# FPGA_BANK_A.net
KiCad netlist of a schematic drawn in Altium Designer
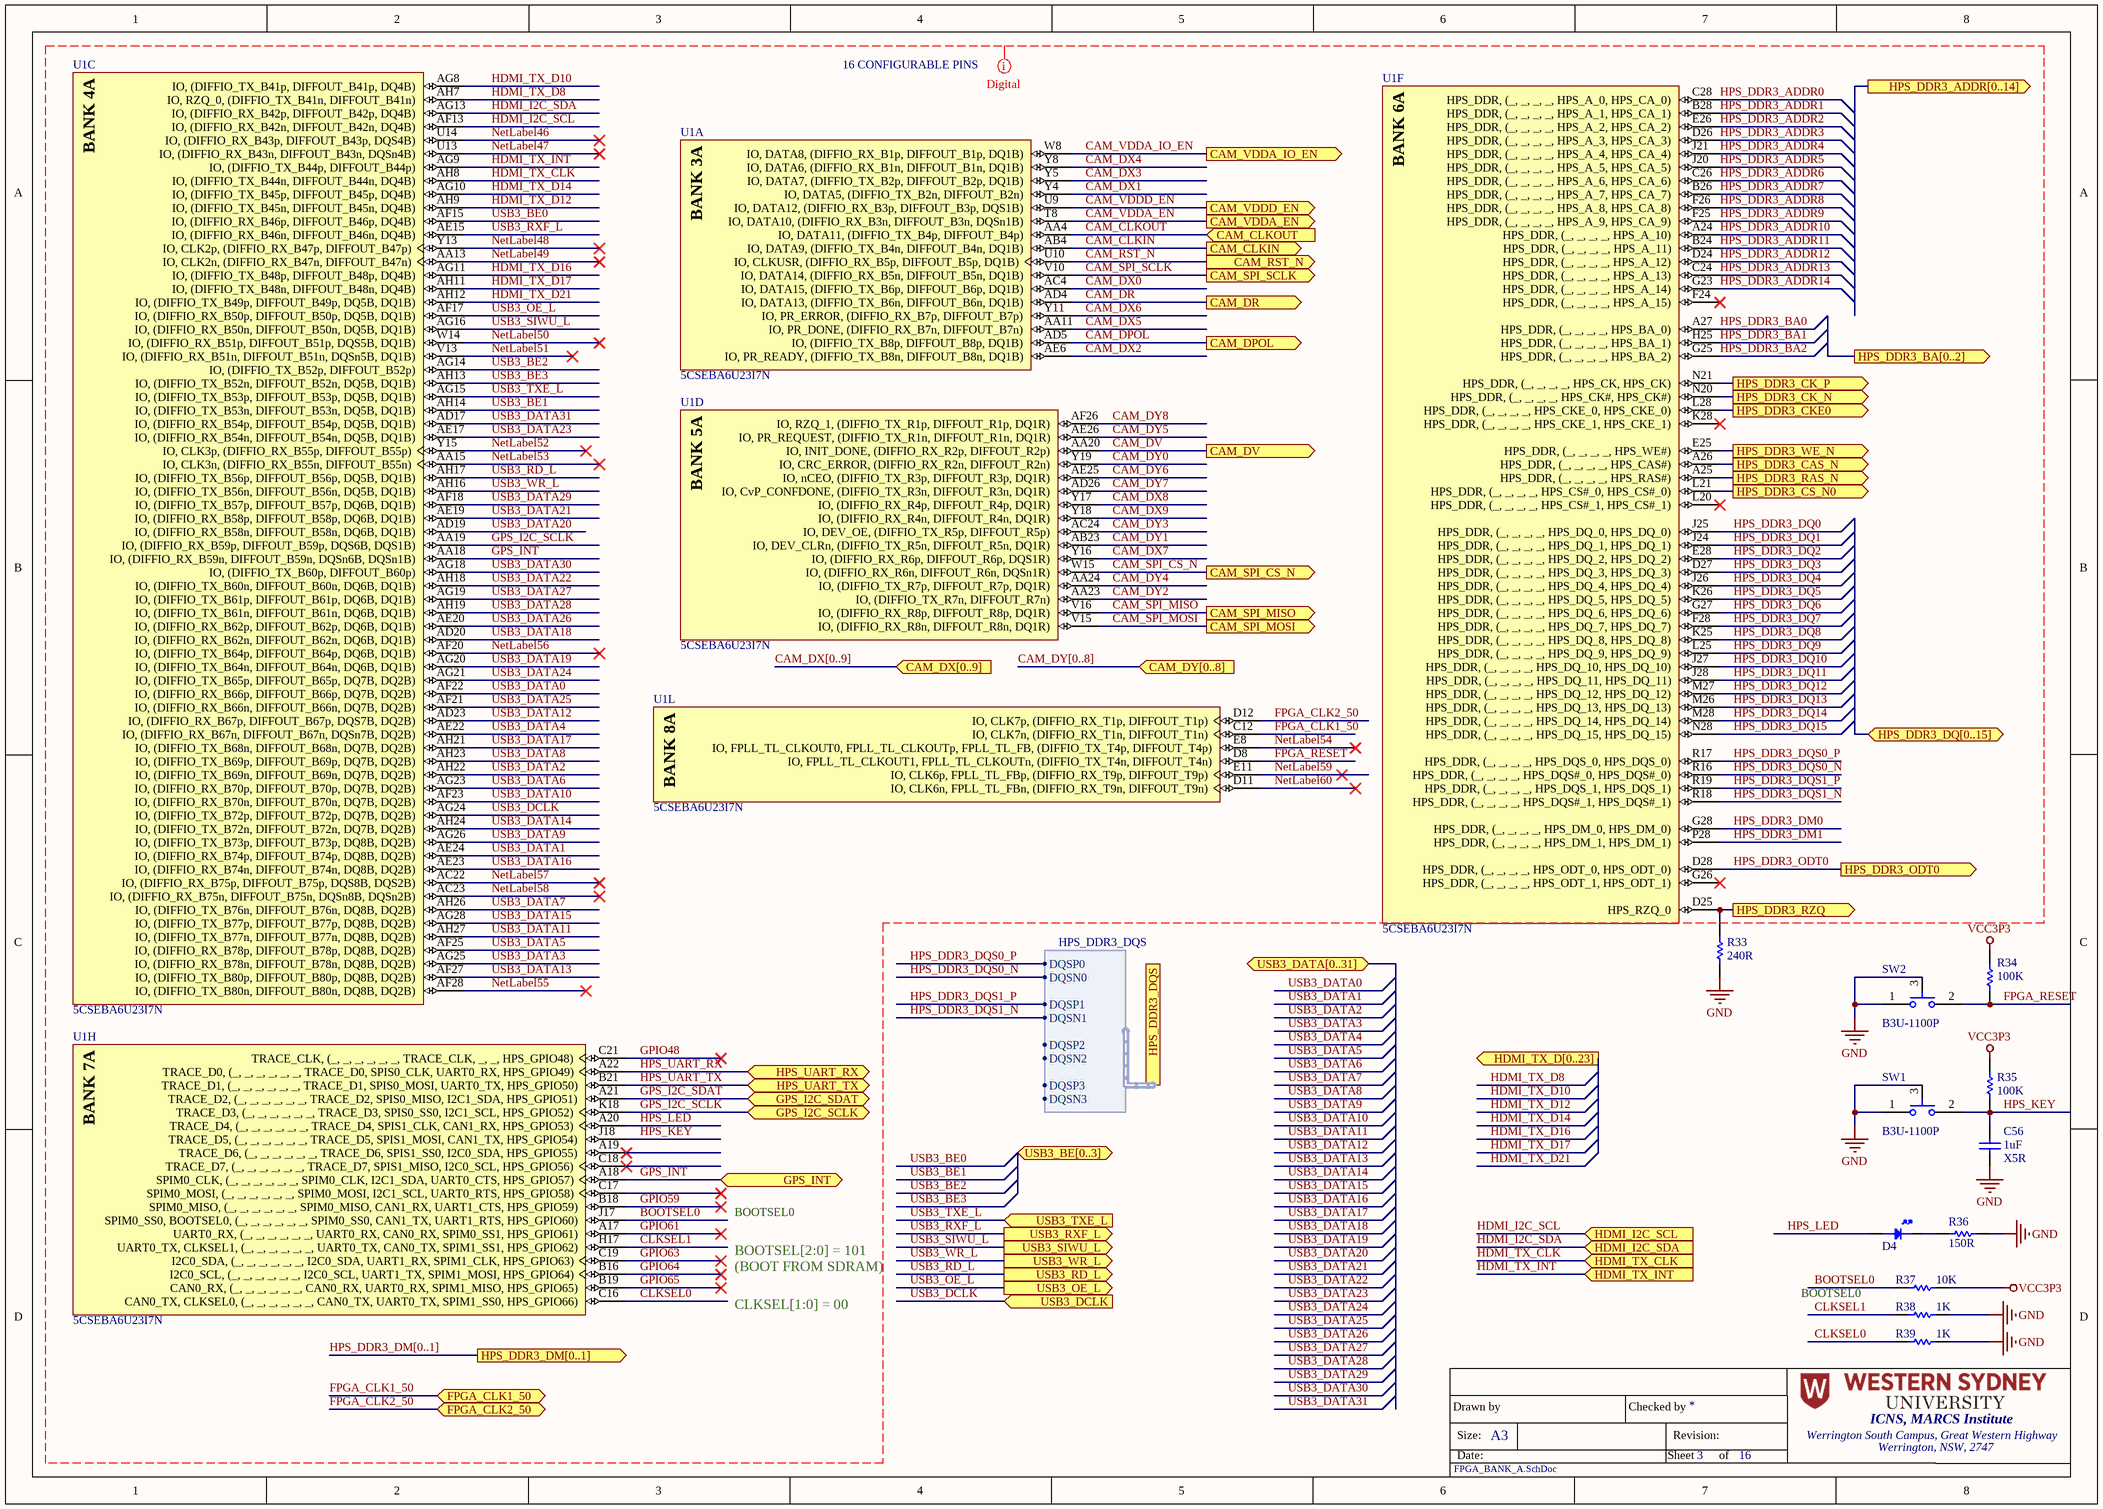
[diagram p0: FPGA_BANK_A.SchDoc]

(export (version "E")
  (design (tool "Eeschema 10.0.6"))
  (components
    (comp (ref "C56")
      (value "1uF")
      (footprint "CAP 0201 (0603)")
      (description "Cap Ceramic 1uF 10V X5R 10% Pad SMD 0201 85C T/R")
      (fields
        (field (name "MANUFACTURER") "Samsung")
        (field (name "TOLERANCE") "10%")
        (field (name "DIELECTRIC") "X5R")
        (field (name "SOURCE") "ICNS_PropheseeLib.SchLib")
      )
      (libsource (lib "") (part "Symbol_1"))
    )
    (comp (ref "D4")
      (value "150060SS75000")
      (footprint "DIOC 0603 (1608)")
      (description "Led, Red, 630 Nm, 1.9 V, 20mA, 30 Ma, 60 Mcd Rohs Compliant: Yes")
      (fields (field (name "SOURCE") "ICNS_PropheseeLib.SchLib"))
      (libsource (lib "Western Sydney University - ICNS") (part "150060SS75000"))
    )
    (comp (ref "R33")
      (value "240R")
      (footprint "RES 0201 (0603)")
      (description "Res Thick Film 0201 240 Ohm 1% 0.05W(1/20W) ±200ppm/C Pad SMD Automotive T/R")
      (fields
        (field (name "MANUFACTURER") "Yageo")
        (field (name "TOLERANCE") "1%")
        (field (name "SOURCE") "ICNS_PropheseeLib.SchLib")
      )
      (libsource (lib "Western Sydney University - ICNS") (part "Symbol"))
    )
    (comp (ref "R34")
      (value "100K")
      (footprint "RES 0402 (1005)")
      (description "Res Thick Film 0402 100K Ohm 1% 0.2W(1/5W) ±100ppm/C Pad SMD Automotive T/R")
      (fields
        (field (name "TOLERANCE") "1%")
        (field (name "Comment") "CRCW0402100KFKEDHP")
        (field (name "SOURCE") "ICNS_PropheseeLib.SchLib")
      )
      (libsource (lib "Western Sydney University - ICNS") (part "Symbol"))
    )
    (comp (ref "R35")
      (value "100K")
      (footprint "RES 0402 (1005)")
      (description "Res Thick Film 0402 100K Ohm 1% 0.2W(1/5W) ±100ppm/C Pad SMD Automotive T/R")
      (fields
        (field (name "TOLERANCE") "1%")
        (field (name "Comment") "CRCW0402100KFKEDHP")
        (field (name "SOURCE") "ICNS_PropheseeLib.SchLib")
      )
      (libsource (lib "Western Sydney University - ICNS") (part "Symbol"))
    )
    (comp (ref "R36")
      (value "AC0603FR-10150RL")
      (footprint "RES 0603 (1608)")
      (description "Chip Resistor Automotive Grade Thick Film 0603 150Ohm 1% Paper T/R")
      (fields
        (field (name "MANUFACTURER") "Yageo")
        (field (name "RESISTANCE") "150R")
        (field (name "TOLERANCE") "1%")
        (field (name "SOURCE") "ICNS_PropheseeLib.SchLib")
      )
      (libsource (lib "Western Sydney University - ICNS") (part "AC0603FR-10150RL"))
    )
    (comp (ref "R37")
      (value "10K")
      (footprint "RES 0201 (0603)")
      (description "Res Thick Film 0201 10K Ohm 1% 0.05W(1/20W) ±200ppm/C Pad SMD Automotive T/R")
      (fields
        (field (name "TOLERANCE") "1%")
        (field (name "MANUFACTURER PART NUMBER") "AC0201FR-0710KL")
        (field (name "SOURCE") "ICNS_PropheseeLib.SchLib")
      )
      (libsource (lib "Western Sydney University - ICNS") (part "Symbol"))
    )
    (comp (ref "R38")
      (value "1K")
      (footprint "RES 0201 (0603)")
      (description "Res Thick Film 0201 1K Ohm 1% 0.05W(1/20W) ±200ppm/C Pad SMD Automotive T/R")
      (fields
        (field (name "MANUFACTURER") "Yageo")
        (field (name "TOLERANCE") "1%")
        (field (name "SOURCE") "ICNS_PropheseeLib.SchLib")
      )
      (libsource (lib "Western Sydney University - ICNS") (part "Symbol"))
    )
    (comp (ref "R39")
      (value "1K")
      (footprint "RES 0201 (0603)")
      (description "Res Thick Film 0201 1K Ohm 1% 0.05W(1/20W) ±200ppm/C Pad SMD Automotive T/R")
      (fields
        (field (name "MANUFACTURER") "Yageo")
        (field (name "TOLERANCE") "1%")
        (field (name "SOURCE") "ICNS_PropheseeLib.SchLib")
      )
      (libsource (lib "Western Sydney University - ICNS") (part "Symbol"))
    )
    (comp (ref "SW1")
      (value "B3U-1100P")
      (footprint "FP-B3U-1100P-MFG")
      (description "Switch Tactile N.O. SPST Round Button Gull Wing 0.05A 12VDC 1.5N SMD Embossed T/R")
      (fields (field (name "MANUFACTURER") "Omron") (field (name "SOURCE") "ICNS_PropheseeLib.SchLib"))
      (libsource (lib "Western Sydney University - ICNS") (part "B3U-1100P"))
    )
    (comp (ref "SW2")
      (value "B3U-1100P")
      (footprint "FP-B3U-1100P-MFG")
      (description "Switch Tactile N.O. SPST Round Button Gull Wing 0.05A 12VDC 1.5N SMD Embossed T/R")
      (fields (field (name "MANUFACTURER") "Omron") (field (name "SOURCE") "ICNS_PropheseeLib.SchLib"))
      (libsource (lib "Western Sydney University - ICNS") (part "B3U-1100P"))
    )
    (comp (ref "U1")
      (value "5CSEBA6U23I7N")
      (footprint "ALTR-UBGA672_A-185")
      (fields (field (name "MANUFACTURER") "Altera") (field (name "SOURCE") "ICNS_PropheseeLib.SchLib"))
      (libsource (lib "Western Sydney University - ICNS") (part "5CSEBA6U23I7N"))
    )
  )
  (nets
    (net (code "19") (name "/BOOTSEL0") (class "Default")
      (node (ref "R37") (pin "2") (pinfunction "2_2") (pintype "passive"))
      (node (ref "U1") (pin "J17") (pinfunction "SPIM0_SS0,_BOOTSEL0,_(_,__,__,__,__,__,_SPIM0_SS0,_CAN1_TX,_UART1_RTS,_HPS_GPIO60)_J17") (pintype "bidirectional"))
    )
    (net (code "20") (name "/CAM_CLKIN") (class "Default")
      (node (ref "U1") (pin "AB4") (pinfunction "IO,_DATA9,_(DIFFIO_TX_B4n,_DIFFOUT_B4n,_DQ1B)_AB4") (pintype "bidirectional"))
    )
    (net (code "21") (name "/CAM_CLKOUT") (class "Default")
      (node (ref "U1") (pin "AA4") (pinfunction "IO,_DATA11,_(DIFFIO_TX_B4p,_DIFFOUT_B4p)_AA4") (pintype "bidirectional"))
    )
    (net (code "22") (name "/CAM_DPOL") (class "Default")
      (node (ref "U1") (pin "AD5") (pinfunction "IO,_(DIFFIO_TX_B8p,_DIFFOUT_B8p,_DQ1B)_AD5") (pintype "bidirectional"))
    )
    (net (code "23") (name "/CAM_DR") (class "Default")
      (node (ref "U1") (pin "AD4") (pinfunction "IO,_DATA13,_(DIFFIO_TX_B6n,_DIFFOUT_B6n,_DQ1B)_AD4") (pintype "bidirectional"))
    )
    (net (code "24") (name "/CAM_DV") (class "Default")
      (node (ref "U1") (pin "AA20") (pinfunction "IO,_INIT_DONE,_(DIFFIO_RX_R2p,_DIFFOUT_R2p)_AA20") (pintype "bidirectional"))
    )
    (net (code "25") (name "/CAM_DX0") (class "Default")
      (node (ref "U1") (pin "AC4") (pinfunction "IO,_DATA15,_(DIFFIO_TX_B6p,_DIFFOUT_B6p,_DQ1B)_AC4") (pintype "bidirectional"))
    )
    (net (code "26") (name "/CAM_DX1") (class "Default")
      (node (ref "U1") (pin "Y4") (pinfunction "IO,_DATA5,_(DIFFIO_TX_B2n,_DIFFOUT_B2n)_Y4") (pintype "bidirectional"))
    )
    (net (code "27") (name "/CAM_DX2") (class "Default")
      (node (ref "U1") (pin "AE6") (pinfunction "IO,_PR_READY,_(DIFFIO_TX_B8n,_DIFFOUT_B8n,_DQ1B)_AE6") (pintype "bidirectional"))
    )
    (net (code "28") (name "/CAM_DX3") (class "Default")
      (node (ref "U1") (pin "Y5") (pinfunction "IO,_DATA7,_(DIFFIO_TX_B2p,_DIFFOUT_B2p,_DQ1B)_Y5") (pintype "bidirectional"))
    )
    (net (code "29") (name "/CAM_DX4") (class "Default")
      (node (ref "U1") (pin "Y8") (pinfunction "IO,_DATA6,_(DIFFIO_RX_B1n,_DIFFOUT_B1n,_DQ1B)_Y8") (pintype "bidirectional"))
    )
    (net (code "30") (name "/CAM_DX5") (class "Default")
      (node (ref "U1") (pin "AA11") (pinfunction "IO,_PR_DONE,_(DIFFIO_RX_B7n,_DIFFOUT_B7n)_AA11") (pintype "bidirectional"))
    )
    (net (code "31") (name "/CAM_DX6") (class "Default")
      (node (ref "U1") (pin "Y11") (pinfunction "IO,_PR_ERROR,_(DIFFIO_RX_B7p,_DIFFOUT_B7p)_Y11") (pintype "bidirectional"))
    )
    (net (code "32") (name "/CAM_DX7") (class "Default")
      (node (ref "U1") (pin "Y16") (pinfunction "IO,_(DIFFIO_RX_R6p,_DIFFOUT_R6p,_DQS1R)_Y16") (pintype "bidirectional"))
    )
    (net (code "33") (name "/CAM_DX8") (class "Default")
      (node (ref "U1") (pin "Y17") (pinfunction "IO,_(DIFFIO_RX_R4p,_DIFFOUT_R4p,_DQ1R)_Y17") (pintype "bidirectional"))
    )
    (net (code "34") (name "/CAM_DX9") (class "Default")
      (node (ref "U1") (pin "Y18") (pinfunction "IO,_(DIFFIO_RX_R4n,_DIFFOUT_R4n,_DQ1R)_Y18") (pintype "bidirectional"))
    )
    (net (code "36") (name "/CAM_DY0") (class "Default")
      (node (ref "U1") (pin "Y19") (pinfunction "IO,_CRC_ERROR,_(DIFFIO_RX_R2n,_DIFFOUT_R2n)_Y19") (pintype "bidirectional"))
    )
    (net (code "37") (name "/CAM_DY1") (class "Default")
      (node (ref "U1") (pin "AB23") (pinfunction "IO,_DEV_CLRn,_(DIFFIO_TX_R5n,_DIFFOUT_R5n,_DQ1R)_AB23") (pintype "bidirectional"))
    )
    (net (code "38") (name "/CAM_DY2") (class "Default")
      (node (ref "U1") (pin "AA23") (pinfunction "IO,_(DIFFIO_TX_R7n,_DIFFOUT_R7n)_AA23") (pintype "bidirectional"))
    )
    (net (code "39") (name "/CAM_DY3") (class "Default")
      (node (ref "U1") (pin "AC24") (pinfunction "IO,_DEV_OE,_(DIFFIO_TX_R5p,_DIFFOUT_R5p)_AC24") (pintype "bidirectional"))
    )
    (net (code "40") (name "/CAM_DY4") (class "Default")
      (node (ref "U1") (pin "AA24") (pinfunction "IO,_(DIFFIO_TX_R7p,_DIFFOUT_R7p,_DQ1R)_AA24") (pintype "bidirectional"))
    )
    (net (code "41") (name "/CAM_DY5") (class "Default")
      (node (ref "U1") (pin "AE26") (pinfunction "IO,_PR_REQUEST,_(DIFFIO_TX_R1n,_DIFFOUT_R1n,_DQ1R)_AE26") (pintype "bidirectional"))
    )
    (net (code "42") (name "/CAM_DY6") (class "Default")
      (node (ref "U1") (pin "AE25") (pinfunction "IO,_nCEO,_(DIFFIO_TX_R3p,_DIFFOUT_R3p,_DQ1R)_AE25") (pintype "bidirectional"))
    )
    (net (code "43") (name "/CAM_DY7") (class "Default")
      (node (ref "U1") (pin "AD26") (pinfunction "IO,_CvP_CONFDONE,_(DIFFIO_TX_R3n,_DIFFOUT_R3n,_DQ1R)_AD26") (pintype "bidirectional"))
    )
    (net (code "44") (name "/CAM_DY8") (class "Default")
      (node (ref "U1") (pin "AF26") (pinfunction "IO,_RZQ_1,_(DIFFIO_TX_R1p,_DIFFOUT_R1p,_DQ1R)_AF26") (pintype "bidirectional"))
    )
    (net (code "46") (name "/CAM_RST_N") (class "Default")
      (node (ref "U1") (pin "U10") (pinfunction "IO,_CLKUSR,_(DIFFIO_RX_B5p,_DIFFOUT_B5p,_DQ1B)_U10") (pintype "bidirectional"))
    )
    (net (code "47") (name "/CAM_SPI_CS_N") (class "Default")
      (node (ref "U1") (pin "W15") (pinfunction "IO,_(DIFFIO_RX_R6n,_DIFFOUT_R6n,_DQSn1R)_W15") (pintype "bidirectional"))
    )
    (net (code "48") (name "/CAM_SPI_MISO") (class "Default")
      (node (ref "U1") (pin "V16") (pinfunction "IO,_(DIFFIO_RX_R8p,_DIFFOUT_R8p,_DQ1R)_V16") (pintype "bidirectional"))
    )
    (net (code "49") (name "/CAM_SPI_MOSI") (class "Default")
      (node (ref "U1") (pin "V15") (pinfunction "IO,_(DIFFIO_RX_R8n,_DIFFOUT_R8n,_DQ1R)_V15") (pintype "bidirectional"))
    )
    (net (code "50") (name "/CAM_SPI_SCLK") (class "Default")
      (node (ref "U1") (pin "V10") (pinfunction "IO,_DATA14,_(DIFFIO_RX_B5n,_DIFFOUT_B5n,_DQ1B)_V10") (pintype "bidirectional"))
    )
    (net (code "51") (name "/CAM_VDDA_EN") (class "Default")
      (node (ref "U1") (pin "T8") (pinfunction "IO,_DATA10,_(DIFFIO_RX_B3n,_DIFFOUT_B3n,_DQSn1B)_T8") (pintype "bidirectional"))
    )
    (net (code "52") (name "/CAM_VDDA_IO_EN") (class "Default")
      (node (ref "U1") (pin "W8") (pinfunction "IO,_DATA8,_(DIFFIO_RX_B1p,_DIFFOUT_B1p,_DQ1B)_W8") (pintype "bidirectional"))
    )
    (net (code "53") (name "/CAM_VDDD_EN") (class "Default")
      (node (ref "U1") (pin "U9") (pinfunction "IO,_DATA12,_(DIFFIO_RX_B3p,_DIFFOUT_B3p,_DQS1B)_U9") (pintype "bidirectional"))
    )
    (net (code "54") (name "/CLKSEL0") (class "Default")
      (node (ref "R39") (pin "1") (pinfunction "1_1") (pintype "passive"))
      (node (ref "U1") (pin "C16") (pinfunction "CAN0_TX,_CLKSEL0,_(_,__,__,__,__,__,_CAN0_TX,_UART0_TX,_SPIM1_SS0,_HPS_GPIO66)_C16") (pintype "bidirectional"))
    )
    (net (code "55") (name "/CLKSEL1") (class "Default")
      (node (ref "R38") (pin "1") (pinfunction "1_1") (pintype "passive"))
      (node (ref "U1") (pin "H17") (pinfunction "UART0_TX,_CLKSEL1,_(_,__,__,__,__,__,_UART0_TX,_CAN0_TX,_SPIM1_SS1,_HPS_GPIO62)_H17") (pintype "bidirectional"))
    )
    (net (code "56") (name "/FPGA_CLK1_50") (class "Default")
      (node (ref "U1") (pin "C12") (pinfunction "IO,_CLK7n,_(DIFFIO_RX_T1n,_DIFFOUT_T1n)_C12") (pintype "bidirectional"))
    )
    (net (code "57") (name "/FPGA_CLK2_50") (class "Default")
      (node (ref "U1") (pin "D12") (pinfunction "IO,_CLK7p,_(DIFFIO_RX_T1p,_DIFFOUT_T1p)_D12") (pintype "bidirectional"))
    )
    (net (code "58") (name "/FPGA_RESET") (class "Default")
      (node (ref "R34") (pin "1") (pinfunction "1_1") (pintype "passive"))
      (node (ref "SW2") (pin "2") (pinfunction "2_2") (pintype "passive"))
      (node (ref "U1") (pin "D8") (pinfunction "IO,_FPLL_TL_CLKOUT1,_FPLL_TL_CLKOUTn,_(DIFFIO_TX_T4n,_DIFFOUT_T4n)_D8") (pintype "bidirectional"))
    )
    (net (code "59") (name "/GPIO48") (class "Default")
      (node (ref "U1") (pin "C21") (pinfunction "TRACE_CLK,_(_,__,__,__,__,__,_TRACE_CLK,__,__,_HPS_GPIO48)_C21") (pintype "bidirectional+no_connect"))
    )
    (net (code "60") (name "/GPIO59") (class "Default")
      (node (ref "U1") (pin "B18") (pinfunction "SPIM0_MISO,_(_,__,__,__,__,__,_SPIM0_MISO,_CAN1_RX,_UART1_CTS,_HPS_GPIO59)_B18") (pintype "bidirectional+no_connect"))
    )
    (net (code "61") (name "/GPIO61") (class "Default")
      (node (ref "U1") (pin "A17") (pinfunction "UART0_RX,_(_,__,__,__,__,__,_UART0_RX,_CAN0_RX,_SPIM0_SS1,_HPS_GPIO61)_A17") (pintype "bidirectional+no_connect"))
    )
    (net (code "62") (name "/GPIO63") (class "Default")
      (node (ref "U1") (pin "C19") (pinfunction "I2C0_SDA,_(_,__,__,__,__,__,_I2C0_SDA,_UART1_RX,_SPIM1_CLK,_HPS_GPIO63)_C19") (pintype "bidirectional+no_connect"))
    )
    (net (code "63") (name "/GPIO64") (class "Default")
      (node (ref "U1") (pin "B16") (pinfunction "I2C0_SCL,_(_,__,__,__,__,__,_I2C0_SCL,_UART1_TX,_SPIM1_MOSI,_HPS_GPIO64)_B16") (pintype "bidirectional+no_connect"))
    )
    (net (code "64") (name "/GPIO65") (class "Default")
      (node (ref "U1") (pin "B19") (pinfunction "CAN0_RX,_(_,__,__,__,__,__,_CAN0_RX,_UART0_RX,_SPIM1_MISO,_HPS_GPIO65)_B19") (pintype "bidirectional+no_connect"))
    )
    (net (code "65") (name "/GPS_I2C_SCLK") (class "Default")
      (node (ref "U1") (pin "AA19") (pinfunction "IO,_(DIFFIO_RX_B59p,_DIFFOUT_B59p,_DQS6B,_DQS1B)_AA19") (pintype "bidirectional"))
      (node (ref "U1") (pin "K18") (pinfunction "TRACE_D3,_(_,__,__,__,__,__,_TRACE_D3,_SPIS0_SS0,_I2C1_SCL,_HPS_GPIO52)_K18") (pintype "bidirectional"))
    )
    (net (code "66") (name "/GPS_I2C_SDAT") (class "Default")
      (node (ref "U1") (pin "A21") (pinfunction "TRACE_D2,_(_,__,__,__,__,__,_TRACE_D2,_SPIS0_MISO,_I2C1_SDA,_HPS_GPIO51)_A21") (pintype "bidirectional"))
    )
    (net (code "67") (name "/GPS_INT") (class "Default")
      (node (ref "U1") (pin "A18") (pinfunction "SPIM0_CLK,_(_,__,__,__,__,__,_SPIM0_CLK,_I2C1_SDA,_UART0_CTS,_HPS_GPIO57)_A18") (pintype "bidirectional"))
      (node (ref "U1") (pin "AA18") (pinfunction "IO,_(DIFFIO_RX_B59n,_DIFFOUT_B59n,_DQSn6B,_DQSn1B)_AA18") (pintype "bidirectional"))
    )
    (net (code "68") (name "/HDMI_I2C_SCL") (class "Default")
      (node (ref "U1") (pin "AF13") (pinfunction "IO,_(DIFFIO_RX_B42n,_DIFFOUT_B42n,_DQ4B)_AF13") (pintype "bidirectional"))
    )
    (net (code "69") (name "/HDMI_I2C_SDA") (class "Default")
      (node (ref "U1") (pin "AG13") (pinfunction "IO,_(DIFFIO_RX_B42p,_DIFFOUT_B42p,_DQ4B)_AG13") (pintype "bidirectional"))
    )
    (net (code "70") (name "/HDMI_TX_CLK") (class "Default")
      (node (ref "U1") (pin "AH8") (pinfunction "IO,_(DIFFIO_TX_B44n,_DIFFOUT_B44n,_DQ4B)_AH8") (pintype "bidirectional"))
    )
    (net (code "71") (name "/HDMI_TX_D8") (class "Default")
      (node (ref "U1") (pin "AH7") (pinfunction "IO,_RZQ_0,_(DIFFIO_TX_B41n,_DIFFOUT_B41n)_AH7") (pintype "bidirectional"))
    )
    (net (code "72") (name "/HDMI_TX_D10") (class "Default")
      (node (ref "U1") (pin "AG8") (pinfunction "IO,_(DIFFIO_TX_B41p,_DIFFOUT_B41p,_DQ4B)_AG8") (pintype "bidirectional"))
    )
    (net (code "73") (name "/HDMI_TX_D12") (class "Default")
      (node (ref "U1") (pin "AH9") (pinfunction "IO,_(DIFFIO_TX_B45n,_DIFFOUT_B45n,_DQ4B)_AH9") (pintype "bidirectional"))
    )
    (net (code "74") (name "/HDMI_TX_D14") (class "Default")
      (node (ref "U1") (pin "AG10") (pinfunction "IO,_(DIFFIO_TX_B45p,_DIFFOUT_B45p,_DQ4B)_AG10") (pintype "bidirectional"))
    )
    (net (code "75") (name "/HDMI_TX_D16") (class "Default")
      (node (ref "U1") (pin "AG11") (pinfunction "IO,_(DIFFIO_TX_B48p,_DIFFOUT_B48p,_DQ4B)_AG11") (pintype "bidirectional"))
    )
    (net (code "76") (name "/HDMI_TX_D17") (class "Default")
      (node (ref "U1") (pin "AH11") (pinfunction "IO,_(DIFFIO_TX_B48n,_DIFFOUT_B48n,_DQ4B)_AH11") (pintype "bidirectional"))
    )
    (net (code "77") (name "/HDMI_TX_D21") (class "Default")
      (node (ref "U1") (pin "AH12") (pinfunction "IO,_(DIFFIO_TX_B49p,_DIFFOUT_B49p,_DQ5B,_DQ1B)_AH12") (pintype "bidirectional"))
    )
    (net (code "79") (name "/HDMI_TX_INT") (class "Default")
      (node (ref "U1") (pin "AG9") (pinfunction "IO,_(DIFFIO_TX_B44p,_DIFFOUT_B44p)_AG9") (pintype "bidirectional"))
    )
    (net (code "80") (name "/HPS_DDR3_ADDR0") (class "Default")
      (node (ref "U1") (pin "C28") (pinfunction "HPS_DDR,_(_,__,__,__,_HPS_A_0,_HPS_CA_0)_C28") (pintype "bidirectional"))
    )
    (net (code "81") (name "/HPS_DDR3_ADDR1") (class "Default")
      (node (ref "U1") (pin "B28") (pinfunction "HPS_DDR,_(_,__,__,__,_HPS_A_1,_HPS_CA_1)_B28") (pintype "bidirectional"))
    )
    (net (code "82") (name "/HPS_DDR3_ADDR2") (class "Default")
      (node (ref "U1") (pin "E26") (pinfunction "HPS_DDR,_(_,__,__,__,_HPS_A_2,_HPS_CA_2)_E26") (pintype "bidirectional"))
    )
    (net (code "83") (name "/HPS_DDR3_ADDR3") (class "Default")
      (node (ref "U1") (pin "D26") (pinfunction "HPS_DDR,_(_,__,__,__,_HPS_A_3,_HPS_CA_3)_D26") (pintype "bidirectional"))
    )
    (net (code "84") (name "/HPS_DDR3_ADDR4") (class "Default")
      (node (ref "U1") (pin "J21") (pinfunction "HPS_DDR,_(_,__,__,__,_HPS_A_4,_HPS_CA_4)_J21") (pintype "bidirectional"))
    )
    (net (code "85") (name "/HPS_DDR3_ADDR5") (class "Default")
      (node (ref "U1") (pin "J20") (pinfunction "HPS_DDR,_(_,__,__,__,_HPS_A_5,_HPS_CA_5)_J20") (pintype "bidirectional"))
    )
    (net (code "86") (name "/HPS_DDR3_ADDR6") (class "Default")
      (node (ref "U1") (pin "C26") (pinfunction "HPS_DDR,_(_,__,__,__,_HPS_A_6,_HPS_CA_6)_C26") (pintype "bidirectional"))
    )
    (net (code "87") (name "/HPS_DDR3_ADDR7") (class "Default")
      (node (ref "U1") (pin "B26") (pinfunction "HPS_DDR,_(_,__,__,__,_HPS_A_7,_HPS_CA_7)_B26") (pintype "bidirectional"))
    )
    (net (code "88") (name "/HPS_DDR3_ADDR8") (class "Default")
      (node (ref "U1") (pin "F26") (pinfunction "HPS_DDR,_(_,__,__,__,_HPS_A_8,_HPS_CA_8)_F26") (pintype "bidirectional"))
    )
    (net (code "89") (name "/HPS_DDR3_ADDR9") (class "Default")
      (node (ref "U1") (pin "F25") (pinfunction "HPS_DDR,_(_,__,__,__,_HPS_A_9,_HPS_CA_9)_F25") (pintype "bidirectional"))
    )
    (net (code "90") (name "/HPS_DDR3_ADDR10") (class "Default")
      (node (ref "U1") (pin "A24") (pinfunction "HPS_DDR,_(_,__,__,__,_HPS_A_10)_A24") (pintype "bidirectional"))
    )
    (net (code "91") (name "/HPS_DDR3_ADDR11") (class "Default")
      (node (ref "U1") (pin "B24") (pinfunction "HPS_DDR,_(_,__,__,__,_HPS_A_11)_B24") (pintype "bidirectional"))
    )
    (net (code "92") (name "/HPS_DDR3_ADDR12") (class "Default")
      (node (ref "U1") (pin "D24") (pinfunction "HPS_DDR,_(_,__,__,__,_HPS_A_12)_D24") (pintype "bidirectional"))
    )
    (net (code "93") (name "/HPS_DDR3_ADDR13") (class "Default")
      (node (ref "U1") (pin "C24") (pinfunction "HPS_DDR,_(_,__,__,__,_HPS_A_13)_C24") (pintype "bidirectional"))
    )
    (net (code "94") (name "/HPS_DDR3_ADDR14") (class "Default")
      (node (ref "U1") (pin "G23") (pinfunction "HPS_DDR,_(_,__,__,__,_HPS_A_14)_G23") (pintype "bidirectional"))
    )
    (net (code "96") (name "/HPS_DDR3_BA0") (class "Default")
      (node (ref "U1") (pin "A27") (pinfunction "HPS_DDR,_(_,__,__,__,_HPS_BA_0)_A27") (pintype "bidirectional"))
    )
    (net (code "97") (name "/HPS_DDR3_BA1") (class "Default")
      (node (ref "U1") (pin "H25") (pinfunction "HPS_DDR,_(_,__,__,__,_HPS_BA_1)_H25") (pintype "bidirectional"))
    )
    (net (code "98") (name "/HPS_DDR3_BA2") (class "Default")
      (node (ref "U1") (pin "G25") (pinfunction "HPS_DDR,_(_,__,__,__,_HPS_BA_2)_G25") (pintype "bidirectional"))
    )
    (net (code "100") (name "/HPS_DDR3_CAS_N") (class "Default")
      (node (ref "U1") (pin "A26") (pinfunction "HPS_DDR,_(_,__,__,__,_HPS_CAS#)_A26") (pintype "bidirectional"))
    )
    (net (code "101") (name "/HPS_DDR3_CKE0") (class "Default")
      (node (ref "U1") (pin "L28") (pinfunction "HPS_DDR,_(_,__,__,__,_HPS_CKE_0,_HPS_CKE_0)_L28") (pintype "bidirectional"))
    )
    (net (code "102") (name "/HPS_DDR3_CK_N") (class "Default")
      (node (ref "U1") (pin "N20") (pinfunction "HPS_DDR,_(_,__,__,__,_HPS_CK#,_HPS_CK#)_N20") (pintype "bidirectional"))
    )
    (net (code "103") (name "/HPS_DDR3_CK_P") (class "Default")
      (node (ref "U1") (pin "N21") (pinfunction "HPS_DDR,_(_,__,__,__,_HPS_CK,_HPS_CK)_N21") (pintype "bidirectional"))
    )
    (net (code "104") (name "/HPS_DDR3_CS_N0") (class "Default")
      (node (ref "U1") (pin "L21") (pinfunction "HPS_DDR,_(_,__,__,__,_HPS_CS#_0,_HPS_CS#_0)_L21") (pintype "bidirectional"))
    )
    (net (code "105") (name "/HPS_DDR3_DM0") (class "Default")
      (node (ref "U1") (pin "G28") (pinfunction "HPS_DDR,_(_,__,__,__,_HPS_DM_0,_HPS_DM_0)_G28") (pintype "bidirectional"))
    )
    (net (code "106") (name "/HPS_DDR3_DM1") (class "Default")
      (node (ref "U1") (pin "P28") (pinfunction "HPS_DDR,_(_,__,__,__,_HPS_DM_1,_HPS_DM_1)_P28") (pintype "bidirectional"))
    )
    (net (code "108") (name "/HPS_DDR3_DQ0") (class "Default")
      (node (ref "U1") (pin "J25") (pinfunction "HPS_DDR,_(_,__,__,__,_HPS_DQ_0,_HPS_DQ_0)_J25") (pintype "bidirectional"))
    )
    (net (code "109") (name "/HPS_DDR3_DQ1") (class "Default")
      (node (ref "U1") (pin "J24") (pinfunction "HPS_DDR,_(_,__,__,__,_HPS_DQ_1,_HPS_DQ_1)_J24") (pintype "bidirectional"))
    )
    (net (code "110") (name "/HPS_DDR3_DQ2") (class "Default")
      (node (ref "U1") (pin "E28") (pinfunction "HPS_DDR,_(_,__,__,__,_HPS_DQ_2,_HPS_DQ_2)_E28") (pintype "bidirectional"))
    )
    (net (code "111") (name "/HPS_DDR3_DQ3") (class "Default")
      (node (ref "U1") (pin "D27") (pinfunction "HPS_DDR,_(_,__,__,__,_HPS_DQ_3,_HPS_DQ_3)_D27") (pintype "bidirectional"))
    )
    (net (code "112") (name "/HPS_DDR3_DQ4") (class "Default")
      (node (ref "U1") (pin "J26") (pinfunction "HPS_DDR,_(_,__,__,__,_HPS_DQ_4,_HPS_DQ_4)_J26") (pintype "bidirectional"))
    )
    (net (code "113") (name "/HPS_DDR3_DQ5") (class "Default")
      (node (ref "U1") (pin "K26") (pinfunction "HPS_DDR,_(_,__,__,__,_HPS_DQ_5,_HPS_DQ_5)_K26") (pintype "bidirectional"))
    )
    (net (code "114") (name "/HPS_DDR3_DQ6") (class "Default")
      (node (ref "U1") (pin "G27") (pinfunction "HPS_DDR,_(_,__,__,__,_HPS_DQ_6,_HPS_DQ_6)_G27") (pintype "bidirectional"))
    )
    (net (code "115") (name "/HPS_DDR3_DQ7") (class "Default")
      (node (ref "U1") (pin "F28") (pinfunction "HPS_DDR,_(_,__,__,__,_HPS_DQ_7,_HPS_DQ_7)_F28") (pintype "bidirectional"))
    )
    (net (code "116") (name "/HPS_DDR3_DQ8") (class "Default")
      (node (ref "U1") (pin "K25") (pinfunction "HPS_DDR,_(_,__,__,__,_HPS_DQ_8,_HPS_DQ_8)_K25") (pintype "bidirectional"))
    )
    (net (code "117") (name "/HPS_DDR3_DQ9") (class "Default")
      (node (ref "U1") (pin "L25") (pinfunction "HPS_DDR,_(_,__,__,__,_HPS_DQ_9,_HPS_DQ_9)_L25") (pintype "bidirectional"))
    )
    (net (code "118") (name "/HPS_DDR3_DQ10") (class "Default")
      (node (ref "U1") (pin "J27") (pinfunction "HPS_DDR,_(_,__,__,__,_HPS_DQ_10,_HPS_DQ_10)_J27") (pintype "bidirectional"))
    )
    (net (code "119") (name "/HPS_DDR3_DQ11") (class "Default")
      (node (ref "U1") (pin "J28") (pinfunction "HPS_DDR,_(_,__,__,__,_HPS_DQ_11,_HPS_DQ_11)_J28") (pintype "bidirectional"))
    )
    (net (code "120") (name "/HPS_DDR3_DQ12") (class "Default")
      (node (ref "U1") (pin "M27") (pinfunction "HPS_DDR,_(_,__,__,__,_HPS_DQ_12,_HPS_DQ_12)_M27") (pintype "bidirectional"))
    )
    (net (code "121") (name "/HPS_DDR3_DQ13") (class "Default")
      (node (ref "U1") (pin "M26") (pinfunction "HPS_DDR,_(_,__,__,__,_HPS_DQ_13,_HPS_DQ_13)_M26") (pintype "bidirectional"))
    )
    (net (code "122") (name "/HPS_DDR3_DQ14") (class "Default")
      (node (ref "U1") (pin "M28") (pinfunction "HPS_DDR,_(_,__,__,__,_HPS_DQ_14,_HPS_DQ_14)_M28") (pintype "bidirectional"))
    )
    (net (code "123") (name "/HPS_DDR3_DQ15") (class "Default")
      (node (ref "U1") (pin "N28") (pinfunction "HPS_DDR,_(_,__,__,__,_HPS_DQ_15,_HPS_DQ_15)_N28") (pintype "bidirectional"))
    )
    (net (code "124") (name "/HPS_DDR3_DQS0_N") (class "Default")
      (node (ref "U1") (pin "R16") (pinfunction "HPS_DDR,_(_,__,__,__,_HPS_DQS#_0,_HPS_DQS#_0)_R16") (pintype "bidirectional"))
    )
    (net (code "125") (name "/HPS_DDR3_DQS0_P") (class "Default")
      (node (ref "U1") (pin "R17") (pinfunction "HPS_DDR,_(_,__,__,__,_HPS_DQS_0,_HPS_DQS_0)_R17") (pintype "bidirectional"))
    )
    (net (code "126") (name "/HPS_DDR3_DQS1_N") (class "Default")
      (node (ref "U1") (pin "R18") (pinfunction "HPS_DDR,_(_,__,__,__,_HPS_DQS#_1,_HPS_DQS#_1)_R18") (pintype "bidirectional"))
    )
    (net (code "127") (name "/HPS_DDR3_DQS1_P") (class "Default")
      (node (ref "U1") (pin "R19") (pinfunction "HPS_DDR,_(_,__,__,__,_HPS_DQS_1,_HPS_DQS_1)_R19") (pintype "bidirectional"))
    )
    (net (code "129") (name "/HPS_DDR3_ODT0") (class "Default")
      (node (ref "U1") (pin "D28") (pinfunction "HPS_DDR,_(_,__,__,__,_HPS_ODT_0,_HPS_ODT_0)_D28") (pintype "bidirectional"))
    )
    (net (code "130") (name "/HPS_DDR3_RAS_N") (class "Default")
      (node (ref "U1") (pin "A25") (pinfunction "HPS_DDR,_(_,__,__,__,_HPS_RAS#)_A25") (pintype "bidirectional"))
    )
    (net (code "131") (name "/HPS_DDR3_RZQ") (class "Default")
      (node (ref "R33") (pin "1") (pinfunction "1_1") (pintype "passive"))
      (node (ref "U1") (pin "D25") (pinfunction "HPS_RZQ_0_D25") (pintype "bidirectional"))
    )
    (net (code "132") (name "/HPS_DDR3_WE_N") (class "Default")
      (node (ref "U1") (pin "E25") (pinfunction "HPS_DDR,_(_,__,__,__,_HPS_WE#)_E25") (pintype "bidirectional"))
    )
    (net (code "133") (name "/HPS_KEY") (class "Default")
      (node (ref "C56") (pin "2") (pinfunction "2_2") (pintype "passive"))
      (node (ref "R35") (pin "1") (pinfunction "1_1") (pintype "passive"))
      (node (ref "SW1") (pin "2") (pinfunction "2_2") (pintype "passive"))
      (node (ref "U1") (pin "J18") (pinfunction "TRACE_D5,_(_,__,__,__,__,__,_TRACE_D5,_SPIS1_MOSI,_CAN1_TX,_HPS_GPIO54)_J18") (pintype "bidirectional"))
    )
    (net (code "134") (name "/HPS_LED") (class "Default")
      (node (ref "D4") (pin "2") (pinfunction "A_2") (pintype "passive"))
      (node (ref "U1") (pin "A20") (pinfunction "TRACE_D4,_(_,__,__,__,__,__,_TRACE_D4,_SPIS1_CLK,_CAN1_RX,_HPS_GPIO53)_A20") (pintype "bidirectional"))
    )
    (net (code "135") (name "/HPS_UART_RX") (class "Default")
      (node (ref "U1") (pin "A22") (pinfunction "TRACE_D0,_(_,__,__,__,__,__,_TRACE_D0,_SPIS0_CLK,_UART0_RX,_HPS_GPIO49)_A22") (pintype "bidirectional"))
    )
    (net (code "136") (name "/HPS_UART_TX") (class "Default")
      (node (ref "U1") (pin "B21") (pinfunction "TRACE_D1,_(_,__,__,__,__,__,_TRACE_D1,_SPIS0_MOSI,_UART0_TX,_HPS_GPIO50)_B21") (pintype "bidirectional"))
    )
    (net (code "137") (name "/NetLabel46") (class "Default")
      (node (ref "U1") (pin "U14") (pinfunction "IO,_(DIFFIO_RX_B43p,_DIFFOUT_B43p,_DQS4B)_U14") (pintype "bidirectional+no_connect"))
    )
    (net (code "138") (name "/NetLabel47") (class "Default")
      (node (ref "U1") (pin "U13") (pinfunction "IO,_(DIFFIO_RX_B43n,_DIFFOUT_B43n,_DQSn4B)_U13") (pintype "bidirectional+no_connect"))
    )
    (net (code "139") (name "/NetLabel48") (class "Default")
      (node (ref "U1") (pin "Y13") (pinfunction "IO,_CLK2p,_(DIFFIO_RX_B47p,_DIFFOUT_B47p)_Y13") (pintype "bidirectional+no_connect"))
    )
    (net (code "140") (name "/NetLabel49") (class "Default")
      (node (ref "U1") (pin "AA13") (pinfunction "IO,_CLK2n,_(DIFFIO_RX_B47n,_DIFFOUT_B47n)_AA13") (pintype "bidirectional+no_connect"))
    )
    (net (code "141") (name "/NetLabel50") (class "Default")
      (node (ref "U1") (pin "W14") (pinfunction "IO,_(DIFFIO_RX_B51p,_DIFFOUT_B51p,_DQS5B,_DQ1B)_W14") (pintype "bidirectional+no_connect"))
    )
    (net (code "142") (name "/NetLabel51") (class "Default")
      (node (ref "U1") (pin "V13") (pinfunction "IO,_(DIFFIO_RX_B51n,_DIFFOUT_B51n,_DQSn5B,_DQ1B)_V13") (pintype "bidirectional+no_connect"))
    )
    (net (code "143") (name "/NetLabel52") (class "Default")
      (node (ref "U1") (pin "Y15") (pinfunction "IO,_CLK3p,_(DIFFIO_RX_B55p,_DIFFOUT_B55p)_Y15") (pintype "bidirectional+no_connect"))
    )
    (net (code "144") (name "/NetLabel53") (class "Default")
      (node (ref "U1") (pin "AA15") (pinfunction "IO,_CLK3n,_(DIFFIO_RX_B55n,_DIFFOUT_B55n)_AA15") (pintype "bidirectional+no_connect"))
    )
    (net (code "145") (name "/NetLabel54") (class "Default")
      (node (ref "U1") (pin "E8") (pinfunction "IO,_FPLL_TL_CLKOUT0,_FPLL_TL_CLKOUTp,_FPLL_TL_FB,_(DIFFIO_TX_T4p,_DIFFOUT_T4p)_E8") (pintype "bidirectional+no_connect"))
    )
    (net (code "146") (name "/NetLabel55") (class "Default")
      (node (ref "U1") (pin "AF28") (pinfunction "IO,_(DIFFIO_TX_B80n,_DIFFOUT_B80n,_DQ8B,_DQ2B)_AF28") (pintype "bidirectional+no_connect"))
    )
    (net (code "147") (name "/NetLabel56") (class "Default")
      (node (ref "U1") (pin "AF20") (pinfunction "IO,_(DIFFIO_TX_B64p,_DIFFOUT_B64p,_DQ6B,_DQ1B)_AF20") (pintype "bidirectional+no_connect"))
    )
    (net (code "148") (name "/NetLabel57") (class "Default")
      (node (ref "U1") (pin "AC22") (pinfunction "IO,_(DIFFIO_RX_B75p,_DIFFOUT_B75p,_DQS8B,_DQS2B)_AC22") (pintype "bidirectional+no_connect"))
    )
    (net (code "149") (name "/NetLabel58") (class "Default")
      (node (ref "U1") (pin "AC23") (pinfunction "IO,_(DIFFIO_RX_B75n,_DIFFOUT_B75n,_DQSn8B,_DQSn2B)_AC23") (pintype "bidirectional+no_connect"))
    )
    (net (code "150") (name "/NetLabel59") (class "Default")
      (node (ref "U1") (pin "E11") (pinfunction "IO,_CLK6p,_FPLL_TL_FBp,_(DIFFIO_RX_T9p,_DIFFOUT_T9p)_E11") (pintype "bidirectional"))
    )
    (net (code "151") (name "/NetLabel60") (class "Default")
      (node (ref "U1") (pin "D11") (pinfunction "IO,_CLK6n,_FPLL_TL_FBn,_(DIFFIO_RX_T9n,_DIFFOUT_T9n)_D11") (pintype "bidirectional+no_connect"))
    )
    (net (code "152") (name "/USB3_BE0") (class "Default")
      (node (ref "U1") (pin "AF15") (pinfunction "IO,_(DIFFIO_RX_B46p,_DIFFOUT_B46p,_DQ4B)_AF15") (pintype "bidirectional"))
    )
    (net (code "153") (name "/USB3_BE1") (class "Default")
      (node (ref "U1") (pin "AH14") (pinfunction "IO,_(DIFFIO_TX_B53n,_DIFFOUT_B53n,_DQ5B,_DQ1B)_AH14") (pintype "bidirectional"))
    )
    (net (code "154") (name "/USB3_BE2") (class "Default")
      (node (ref "U1") (pin "AG14") (pinfunction "IO,_(DIFFIO_TX_B52p,_DIFFOUT_B52p)_AG14") (pintype "bidirectional"))
    )
    (net (code "155") (name "/USB3_BE3") (class "Default")
      (node (ref "U1") (pin "AH13") (pinfunction "IO,_(DIFFIO_TX_B52n,_DIFFOUT_B52n,_DQ5B,_DQ1B)_AH13") (pintype "bidirectional"))
    )
    (net (code "157") (name "/USB3_DATA0") (class "Default")
      (node (ref "U1") (pin "AF22") (pinfunction "IO,_(DIFFIO_RX_B66p,_DIFFOUT_B66p,_DQ7B,_DQ2B)_AF22") (pintype "bidirectional"))
    )
    (net (code "158") (name "/USB3_DATA1") (class "Default")
      (node (ref "U1") (pin "AE24") (pinfunction "IO,_(DIFFIO_RX_B74p,_DIFFOUT_B74p,_DQ8B,_DQ2B)_AE24") (pintype "bidirectional"))
    )
    (net (code "159") (name "/USB3_DATA2") (class "Default")
      (node (ref "U1") (pin "AH22") (pinfunction "IO,_(DIFFIO_TX_B69n,_DIFFOUT_B69n,_DQ7B,_DQ2B)_AH22") (pintype "bidirectional"))
    )
    (net (code "160") (name "/USB3_DATA3") (class "Default")
      (node (ref "U1") (pin "AG25") (pinfunction "IO,_(DIFFIO_RX_B78n,_DIFFOUT_B78n,_DQ8B,_DQ2B)_AG25") (pintype "bidirectional"))
    )
    (net (code "161") (name "/USB3_DATA4") (class "Default")
      (node (ref "U1") (pin "AE22") (pinfunction "IO,_(DIFFIO_RX_B67n,_DIFFOUT_B67n,_DQSn7B,_DQ2B)_AE22") (pintype "bidirectional"))
    )
    (net (code "162") (name "/USB3_DATA5") (class "Default")
      (node (ref "U1") (pin "AF25") (pinfunction "IO,_(DIFFIO_RX_B78p,_DIFFOUT_B78p,_DQ8B,_DQ2B)_AF25") (pintype "bidirectional"))
    )
    (net (code "163") (name "/USB3_DATA6") (class "Default")
      (node (ref "U1") (pin "AG23") (pinfunction "IO,_(DIFFIO_RX_B70p,_DIFFOUT_B70p,_DQ7B,_DQ2B)_AG23") (pintype "bidirectional"))
    )
    (net (code "164") (name "/USB3_DATA7") (class "Default")
      (node (ref "U1") (pin "AH26") (pinfunction "IO,_(DIFFIO_TX_B76n,_DIFFOUT_B76n,_DQ8B,_DQ2B)_AH26") (pintype "bidirectional"))
    )
    (net (code "165") (name "/USB3_DATA8") (class "Default")
      (node (ref "U1") (pin "AH23") (pinfunction "IO,_(DIFFIO_TX_B69p,_DIFFOUT_B69p,_DQ7B,_DQ2B)_AH23") (pintype "bidirectional"))
    )
    (net (code "166") (name "/USB3_DATA9") (class "Default")
      (node (ref "U1") (pin "AG26") (pinfunction "IO,_(DIFFIO_TX_B73p,_DIFFOUT_B73p,_DQ8B,_DQ2B)_AG26") (pintype "bidirectional"))
    )
    (net (code "167") (name "/USB3_DATA10") (class "Default")
      (node (ref "U1") (pin "AF23") (pinfunction "IO,_(DIFFIO_RX_B70n,_DIFFOUT_B70n,_DQ7B,_DQ2B)_AF23") (pintype "bidirectional"))
    )
    (net (code "168") (name "/USB3_DATA11") (class "Default")
      (node (ref "U1") (pin "AH27") (pinfunction "IO,_(DIFFIO_TX_B77n,_DIFFOUT_B77n,_DQ8B,_DQ2B)_AH27") (pintype "bidirectional"))
    )
    (net (code "169") (name "/USB3_DATA12") (class "Default")
      (node (ref "U1") (pin "AD23") (pinfunction "IO,_(DIFFIO_RX_B67p,_DIFFOUT_B67p,_DQS7B,_DQ2B)_AD23") (pintype "bidirectional"))
    )
    (net (code "170") (name "/USB3_DATA13") (class "Default")
      (node (ref "U1") (pin "AF27") (pinfunction "IO,_(DIFFIO_TX_B80p,_DIFFOUT_B80p,_DQ8B,_DQ2B)_AF27") (pintype "bidirectional"))
    )
    (net (code "171") (name "/USB3_DATA14") (class "Default")
      (node (ref "U1") (pin "AH24") (pinfunction "IO,_(DIFFIO_TX_B72n,_DIFFOUT_B72n,_DQ7B,_DQ2B)_AH24") (pintype "bidirectional"))
    )
    (net (code "172") (name "/USB3_DATA15") (class "Default")
      (node (ref "U1") (pin "AG28") (pinfunction "IO,_(DIFFIO_TX_B77p,_DIFFOUT_B77p,_DQ8B,_DQ2B)_AG28") (pintype "bidirectional"))
    )
    (net (code "173") (name "/USB3_DATA16") (class "Default")
      (node (ref "U1") (pin "AE23") (pinfunction "IO,_(DIFFIO_RX_B74n,_DIFFOUT_B74n,_DQ8B,_DQ2B)_AE23") (pintype "bidirectional"))
    )
    (net (code "174") (name "/USB3_DATA17") (class "Default")
      (node (ref "U1") (pin "AH21") (pinfunction "IO,_(DIFFIO_TX_B68n,_DIFFOUT_B68n,_DQ7B,_DQ2B)_AH21") (pintype "bidirectional"))
    )
    (net (code "175") (name "/USB3_DATA18") (class "Default")
      (node (ref "U1") (pin "AD20") (pinfunction "IO,_(DIFFIO_RX_B62n,_DIFFOUT_B62n,_DQ6B,_DQ1B)_AD20") (pintype "bidirectional"))
    )
    (net (code "176") (name "/USB3_DATA19") (class "Default")
      (node (ref "U1") (pin "AG20") (pinfunction "IO,_(DIFFIO_TX_B64n,_DIFFOUT_B64n,_DQ6B,_DQ1B)_AG20") (pintype "bidirectional"))
    )
    (net (code "177") (name "/USB3_DATA20") (class "Default")
      (node (ref "U1") (pin "AD19") (pinfunction "IO,_(DIFFIO_RX_B58n,_DIFFOUT_B58n,_DQ6B,_DQ1B)_AD19") (pintype "bidirectional"))
    )
    (net (code "178") (name "/USB3_DATA21") (class "Default")
      (node (ref "U1") (pin "AE19") (pinfunction "IO,_(DIFFIO_RX_B58p,_DIFFOUT_B58p,_DQ6B,_DQ1B)_AE19") (pintype "bidirectional"))
    )
    (net (code "179") (name "/USB3_DATA22") (class "Default")
      (node (ref "U1") (pin "AH18") (pinfunction "IO,_(DIFFIO_TX_B60n,_DIFFOUT_B60n,_DQ6B,_DQ1B)_AH18") (pintype "bidirectional"))
    )
    (net (code "180") (name "/USB3_DATA23") (class "Default")
      (node (ref "U1") (pin "AE17") (pinfunction "IO,_(DIFFIO_RX_B54n,_DIFFOUT_B54n,_DQ5B,_DQ1B)_AE17") (pintype "bidirectional"))
    )
    (net (code "181") (name "/USB3_DATA24") (class "Default")
      (node (ref "U1") (pin "AG21") (pinfunction "IO,_(DIFFIO_TX_B65p,_DIFFOUT_B65p,_DQ7B,_DQ2B)_AG21") (pintype "bidirectional"))
    )
    (net (code "182") (name "/USB3_DATA25") (class "Default")
      (node (ref "U1") (pin "AF21") (pinfunction "IO,_(DIFFIO_RX_B66n,_DIFFOUT_B66n,_DQ7B,_DQ2B)_AF21") (pintype "bidirectional"))
    )
    (net (code "183") (name "/USB3_DATA26") (class "Default")
      (node (ref "U1") (pin "AE20") (pinfunction "IO,_(DIFFIO_RX_B62p,_DIFFOUT_B62p,_DQ6B,_DQ1B)_AE20") (pintype "bidirectional"))
    )
    (net (code "184") (name "/USB3_DATA27") (class "Default")
      (node (ref "U1") (pin "AG19") (pinfunction "IO,_(DIFFIO_TX_B61p,_DIFFOUT_B61p,_DQ6B,_DQ1B)_AG19") (pintype "bidirectional"))
    )
    (net (code "185") (name "/USB3_DATA28") (class "Default")
      (node (ref "U1") (pin "AH19") (pinfunction "IO,_(DIFFIO_TX_B61n,_DIFFOUT_B61n,_DQ6B,_DQ1B)_AH19") (pintype "bidirectional"))
    )
    (net (code "186") (name "/USB3_DATA29") (class "Default")
      (node (ref "U1") (pin "AF18") (pinfunction "IO,_(DIFFIO_TX_B57p,_DIFFOUT_B57p,_DQ6B,_DQ1B)_AF18") (pintype "bidirectional"))
    )
    (net (code "187") (name "/USB3_DATA30") (class "Default")
      (node (ref "U1") (pin "AG18") (pinfunction "IO,_(DIFFIO_TX_B60p,_DIFFOUT_B60p)_AG18") (pintype "bidirectional"))
    )
    (net (code "188") (name "/USB3_DATA31") (class "Default")
      (node (ref "U1") (pin "AD17") (pinfunction "IO,_(DIFFIO_RX_B54p,_DIFFOUT_B54p,_DQ5B,_DQ1B)_AD17") (pintype "bidirectional"))
    )
    (net (code "190") (name "/USB3_DCLK") (class "Default")
      (node (ref "U1") (pin "AG24") (pinfunction "IO,_(DIFFIO_TX_B72p,_DIFFOUT_B72p,_DQ7B,_DQ2B)_AG24") (pintype "bidirectional"))
    )
    (net (code "191") (name "/USB3_OE_L") (class "Default")
      (node (ref "U1") (pin "AF17") (pinfunction "IO,_(DIFFIO_RX_B50p,_DIFFOUT_B50p,_DQ5B,_DQ1B)_AF17") (pintype "bidirectional"))
    )
    (net (code "192") (name "/USB3_RD_L") (class "Default")
      (node (ref "U1") (pin "AH17") (pinfunction "IO,_(DIFFIO_TX_B56p,_DIFFOUT_B56p,_DQ5B,_DQ1B)_AH17") (pintype "bidirectional"))
    )
    (net (code "193") (name "/USB3_RXF_L") (class "Default")
      (node (ref "U1") (pin "AE15") (pinfunction "IO,_(DIFFIO_RX_B46n,_DIFFOUT_B46n,_DQ4B)_AE15") (pintype "bidirectional"))
    )
    (net (code "194") (name "/USB3_SIWU_L") (class "Default")
      (node (ref "U1") (pin "AG16") (pinfunction "IO,_(DIFFIO_RX_B50n,_DIFFOUT_B50n,_DQ5B,_DQ1B)_AG16") (pintype "bidirectional"))
    )
    (net (code "195") (name "/USB3_TXE_L") (class "Default")
      (node (ref "U1") (pin "AG15") (pinfunction "IO,_(DIFFIO_TX_B53p,_DIFFOUT_B53p,_DQ5B,_DQ1B)_AG15") (pintype "bidirectional"))
    )
    (net (code "196") (name "/USB3_WR_L") (class "Default")
      (node (ref "U1") (pin "AH16") (pinfunction "IO,_(DIFFIO_TX_B56n,_DIFFOUT_B56n,_DQ5B,_DQ1B)_AH16") (pintype "bidirectional"))
    )
    (net (code "198") (name "GND") (class "Default")
      (node (ref "C56") (pin "1") (pinfunction "1_1") (pintype "passive"))
      (node (ref "R33") (pin "2") (pinfunction "2_2") (pintype "passive"))
      (node (ref "R36") (pin "1") (pinfunction "1_1") (pintype "passive"))
      (node (ref "R38") (pin "2") (pinfunction "2_2") (pintype "passive"))
      (node (ref "R39") (pin "2") (pinfunction "2_2") (pintype "passive"))
      (node (ref "SW1") (pin "1") (pinfunction "1_1") (pintype "passive"))
      (node (ref "SW1") (pin "3") (pinfunction "3_3") (pintype "passive"))
      (node (ref "SW2") (pin "1") (pinfunction "1_1") (pintype "passive"))
      (node (ref "SW2") (pin "3") (pinfunction "3_3") (pintype "passive"))
    )
    (net (code "199") (name "Net-(D4-K)") (class "Default")
      (node (ref "D4") (pin "1") (pinfunction "K_1") (pintype "passive"))
      (node (ref "R36") (pin "2") (pinfunction "2_2") (pintype "passive"))
    )
    (net (code "200") (name "VCC3P3") (class "Default")
      (node (ref "R34") (pin "2") (pinfunction "2_2") (pintype "passive"))
      (node (ref "R35") (pin "2") (pinfunction "2_2") (pintype "passive"))
      (node (ref "R37") (pin "1") (pinfunction "1_1") (pintype "passive"))
    )
    (net (code "201") (name "unconnected-(U1F-HPS_DDR,_(_,__,__,__,_HPS_A_15)-PadF24)") (class "Default")
      (node (ref "U1") (pin "F24") (pinfunction "HPS_DDR,_(_,__,__,__,_HPS_A_15)_F24") (pintype "bidirectional+no_connect"))
    )
    (net (code "202") (name "unconnected-(U1F-HPS_DDR,_(_,__,__,__,_HPS_CKE_1,_HPS_CKE_1)-PadK28)") (class "Default")
      (node (ref "U1") (pin "K28") (pinfunction "HPS_DDR,_(_,__,__,__,_HPS_CKE_1,_HPS_CKE_1)_K28") (pintype "bidirectional+no_connect"))
    )
    (net (code "203") (name "unconnected-(U1F-HPS_DDR,_(_,__,__,__,_HPS_CS#_1,_HPS_CS#_1)-PadL20)") (class "Default")
      (node (ref "U1") (pin "L20") (pinfunction "HPS_DDR,_(_,__,__,__,_HPS_CS#_1,_HPS_CS#_1)_L20") (pintype "bidirectional+no_connect"))
    )
    (net (code "204") (name "unconnected-(U1F-HPS_DDR,_(_,__,__,__,_HPS_ODT_1,_HPS_ODT_1)-PadG26)") (class "Default")
      (node (ref "U1") (pin "G26") (pinfunction "HPS_DDR,_(_,__,__,__,_HPS_ODT_1,_HPS_ODT_1)_G26") (pintype "bidirectional+no_connect"))
    )
    (net (code "205") (name "unconnected-(U1H-SPIM0_MOSI,_(_,__,__,__,__,__,_SPIM0_MOSI,_I2C1_SCL,_UART0_RTS,_HPS_GPIO58)-PadC17)") (class "Default")
      (node (ref "U1") (pin "C17") (pinfunction "SPIM0_MOSI,_(_,__,__,__,__,__,_SPIM0_MOSI,_I2C1_SCL,_UART0_RTS,_HPS_GPIO58)_C17") (pintype "bidirectional+no_connect"))
    )
    (net (code "206") (name "unconnected-(U1H-TRACE_D6,_(_,__,__,__,__,__,_TRACE_D6,_SPIS1_SS0,_I2C0_SDA,_HPS_GPIO55)-PadA19)") (class "Default")
      (node (ref "U1") (pin "A19") (pinfunction "TRACE_D6,_(_,__,__,__,__,__,_TRACE_D6,_SPIS1_SS0,_I2C0_SDA,_HPS_GPIO55)_A19") (pintype "bidirectional+no_connect"))
    )
    (net (code "207") (name "unconnected-(U1H-TRACE_D7,_(_,__,__,__,__,__,_TRACE_D7,_SPIS1_MISO,_I2C0_SCL,_HPS_GPIO56)-PadC18)") (class "Default")
      (node (ref "U1") (pin "C18") (pinfunction "TRACE_D7,_(_,__,__,__,__,__,_TRACE_D7,_SPIS1_MISO,_I2C0_SCL,_HPS_GPIO56)_C18") (pintype "bidirectional+no_connect"))
    )
  )
)
